# msr502.net
KiCad netlist of a schematic drawn in Altium Designer
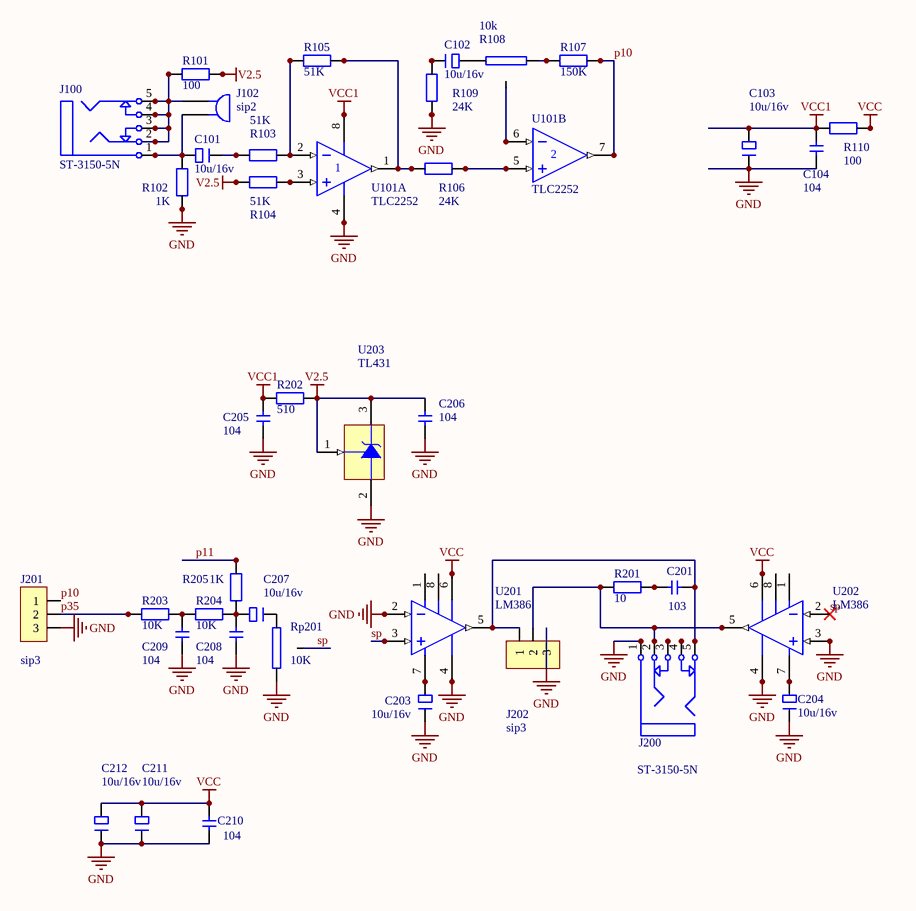
[diagram p0: msr502.SchDoc]

(export (version "E")
  (design (tool "Eeschema 10.0.6"))
  (components
    (comp (ref "C101")
      (value "10u/16v")
      (footprint "rb.1/.2")
      (description "Electrolytic Capacitor")
      (libsource (lib "msr3") (part "ELECTRO1"))
    )
    (comp (ref "C102")
      (value "10u/16v")
      (footprint "rb.1/.2")
      (description "Electrolytic Capacitor")
      (libsource (lib "msr3") (part "ELECTRO1"))
    )
    (comp (ref "C103")
      (value "10u/16v")
      (footprint "rb.1/.2")
      (description "Electrolytic Capacitor")
      (libsource (lib "msr3") (part "ELECTRO1"))
    )
    (comp (ref "C104")
      (value "104")
      (footprint "CAP010805")
      (description "Capacitor")
      (libsource (lib "*") (part "CAP"))
    )
    (comp (ref "C201")
      (value "103")
      (footprint "cap0.1")
      (description "Capacitor")
      (libsource (lib "m2t1") (part "CAP"))
    )
    (comp (ref "C203")
      (value "10u/16v")
      (footprint "rb.1/.2")
      (description "Electrolytic Capacitor")
      (libsource (lib "msr3") (part "ELECTRO1"))
    )
    (comp (ref "C204")
      (value "10u/16v")
      (footprint "rb.1/.2")
      (description "Electrolytic Capacitor")
      (libsource (lib "msr3") (part "ELECTRO1"))
    )
    (comp (ref "C205")
      (value "104")
      (footprint "CAP010805")
      (description "Capacitor")
      (libsource (lib "m2t1") (part "CAP"))
    )
    (comp (ref "C206")
      (value "104")
      (footprint "CAP010805")
      (description "Capacitor")
      (libsource (lib "m2t1") (part "CAP"))
    )
    (comp (ref "C207")
      (value "10u/16v")
      (footprint "rb.1/.2")
      (description "Electrolytic Capacitor")
      (libsource (lib "msr3") (part "ELECTRO1"))
    )
    (comp (ref "C208")
      (value "104")
      (footprint "CAP010805")
      (description "Capacitor")
      (libsource (lib "m2t1") (part "CAP"))
    )
    (comp (ref "C209")
      (value "104")
      (footprint "CAP010805")
      (description "Capacitor")
      (libsource (lib "m2t1") (part "CAP"))
    )
    (comp (ref "C210")
      (value "104")
      (footprint "CAP010805")
      (description "Capacitor")
      (libsource (lib "*") (part "CAP"))
    )
    (comp (ref "C211")
      (value "10u/16v")
      (footprint "rb.1/.2")
      (description "Electrolytic Capacitor")
      (libsource (lib "msr3") (part "ELECTRO1"))
    )
    (comp (ref "C212")
      (value "10u/16v")
      (footprint "rb.1/.2")
      (description "Electrolytic Capacitor")
      (libsource (lib "msr3") (part "ELECTRO1"))
    )
    (comp (ref "J100")
      (value "ST-3150-5N")
      (footprint "ST-3150-5N")
      (description "3-Conductor Jack with 2 break contacts (normals) and 2 auxiliary make contacts")
      (fields (field (name "Comment") "Phonejack Stereo SW") (field (name "PUBLISHER") "Altium Limited"))
      (libsource (lib "mtr1_4") (part "Phonejack Stereo SW"))
    )
    (comp (ref "J102")
      (value "sip2")
      (footprint "PIN2")
      (description "Microphone")
      (fields (field (name "Comment") "pow") (field (name "PUBLISHER") "Altium Limited"))
      (libsource (lib "Miscellaneous Devices") (part "Mic1"))
    )
    (comp (ref "J200")
      (value "ST-3150-5N")
      (footprint "ST-3150-5N")
      (description "3-Conductor Jack with 2 break contacts (normals) and 2 auxiliary make contacts")
      (fields (field (name "Comment") "Phonejack Stereo SW") (field (name "PUBLISHER") "Altium Limited"))
      (libsource (lib "mtr1_4") (part "Phonejack Stereo SW"))
    )
    (comp (ref "J201")
      (value "sip3")
      (footprint "SIP3")
      (description "Connector")
      (fields (field (name "Comment") "CON3"))
      (libsource (lib "m2t1") (part "CON3"))
    )
    (comp (ref "J202")
      (value "sip3")
      (footprint "SIP3")
      (description "Connector")
      (fields (field (name "Comment") "CON3"))
      (libsource (lib "mtr1_1") (part "CON3"))
    )
    (comp (ref "R101")
      (value "100")
      (footprint "a038050")
      (description "Resistor")
      (fields (field (name "Comment") "Res2") (field (name "PUBLISHER") "Altium Limited"))
      (libsource (lib "") (part "Res22_1"))
    )
    (comp (ref "R102")
      (value "1K")
      (footprint "a038050")
      (description "Resistor")
      (fields (field (name "Comment") "Res2") (field (name "PUBLISHER") "Altium Limited"))
      (libsource (lib "") (part "Res22_3"))
    )
    (comp (ref "R103")
      (value "51K")
      (footprint "a038050")
      (description "Resistor")
      (fields (field (name "Comment") "Res2") (field (name "PUBLISHER") "Altium Limited"))
      (libsource (lib "msr4") (part "Res22"))
    )
    (comp (ref "R104")
      (value "51K")
      (footprint "a038050")
      (description "Resistor")
      (fields (field (name "Comment") "Res2") (field (name "PUBLISHER") "Altium Limited"))
      (libsource (lib "msr4") (part "Res22"))
    )
    (comp (ref "R105")
      (value "51K")
      (footprint "a038050")
      (description "Resistor")
      (fields (field (name "Comment") "Res2") (field (name "PUBLISHER") "Altium Limited"))
      (libsource (lib "") (part "Res22_1"))
    )
    (comp (ref "R106")
      (value "24K")
      (footprint "a038050")
      (description "Resistor")
      (fields (field (name "Comment") "Res2") (field (name "PUBLISHER") "Altium Limited"))
      (libsource (lib "") (part "Res22_1"))
    )
    (comp (ref "R107")
      (value "150K")
      (footprint "a038050")
      (description "Resistor")
      (fields (field (name "Comment") "Res2") (field (name "PUBLISHER") "Altium Limited"))
      (libsource (lib "") (part "Res22_1"))
    )
    (comp (ref "R108")
      (value "10k")
      (footprint "VR3296-1")
      (description "3296")
      (libsource (lib "MyLib") (part "RES3"))
    )
    (comp (ref "R109")
      (value "24K")
      (footprint "a038050")
      (description "Resistor")
      (fields (field (name "Comment") "Res2") (field (name "PUBLISHER") "Altium Limited"))
      (libsource (lib "") (part "Res22_2"))
    )
    (comp (ref "R110")
      (value "100")
      (footprint "a038050")
      (description "Resistor")
      (fields (field (name "Comment") "Res2") (field (name "PUBLISHER") "Altium Limited"))
      (libsource (lib "") (part "Res22_1"))
    )
    (comp (ref "R201")
      (value "10")
      (footprint "a038050")
      (description "Resistor")
      (fields (field (name "Comment") "Res2") (field (name "PUBLISHER") "Altium Limited"))
      (libsource (lib "") (part "Res22_1"))
    )
    (comp (ref "R202")
      (value "510")
      (footprint "a038050")
      (description "Resistor")
      (fields (field (name "Comment") "Res2") (field (name "PUBLISHER") "Altium Limited"))
      (libsource (lib "") (part "Res22_1"))
    )
    (comp (ref "R203")
      (value "10K")
      (footprint "a038050")
      (description "Resistor")
      (fields (field (name "Comment") "Res2") (field (name "PUBLISHER") "Altium Limited"))
      (libsource (lib "") (part "Res22_1"))
    )
    (comp (ref "R204")
      (value "10K")
      (footprint "a038050")
      (description "Resistor")
      (fields (field (name "Comment") "Res2") (field (name "PUBLISHER") "Altium Limited"))
      (libsource (lib "") (part "Res22_1"))
    )
    (comp (ref "R205")
      (value "1K")
      (footprint "a038050")
      (description "Resistor")
      (fields (field (name "Comment") "Res2") (field (name "PUBLISHER") "Altium Limited"))
      (libsource (lib "") (part "Res22_2"))
    )
    (comp (ref "Rp201")
      (value "10K")
      (footprint "VR3296-1")
      (description "3296")
      (fields (field (name "Comment") "10k"))
      (libsource (lib "MyLib") (part "RES3"))
    )
    (comp (ref "U101")
      (value "TLC2252")
      (footprint "DS-8")
      (description "Dual Low-Power Operational Amplifier")
      (fields (field (name "PUBLISHER") "Altium Limited"))
      (libsource (lib "msr4") (part "LM358ds"))
    )
    (comp (ref "U201")
      (value "LM386")
      (footprint "DS-8")
      (description "Low Voltage Audio Power Amplifier")
      (fields (field (name "PARTNUMBER") "LM386N-1") (field (name "MANUFACTURER") "National Semiconductor"))
      (libsource (lib "msr4") (part "LM386ds"))
    )
    (comp (ref "U202")
      (value "LM386")
      (footprint "DS-8")
      (description "Low Voltage Audio Power Amplifier")
      (fields (field (name "PARTNUMBER") "LM386N-1") (field (name "MANUFACTURER") "National Semiconductor"))
      (libsource (lib "msr4") (part "LM386ds"))
    )
    (comp (ref "U203")
      (value "TL431")
      (footprint "29-04")
      (description "Programmable Precision Reference")
      (fields (field (name "Comment") "TL431AILP") (field (name "PUBLISHER") "Altium Limited"))
      (libsource (lib "ON Semi Power Mgt Voltage Reference") (part "TL431AILP"))
    )
  )
  (nets
    (net (code "1") (name "/p10") (class "Default")
      (node (ref "J201") (pin "1") (pinfunction "1_1") (pintype "passive"))
      (node (ref "R107") (pin "2") (pinfunction "2_2") (pintype "passive"))
      (node (ref "R107") (pin "4") (pinfunction "4_4") (pintype "passive"))
      (node (ref "U101") (pin "17") (pinfunction "17_17") (pintype "passive"))
      (node (ref "U101") (pin "7") (pinfunction "OUT_7") (pintype "output"))
    )
    (net (code "2") (name "/p11") (class "Default")
      (node (ref "R205") (pin "2") (pinfunction "2_2") (pintype "passive"))
      (node (ref "R205") (pin "4") (pinfunction "4_4") (pintype "passive"))
    )
    (net (code "3") (name "/p35") (class "Default")
      (node (ref "J201") (pin "2") (pinfunction "2_2") (pintype "passive"))
      (node (ref "R203") (pin "1") (pinfunction "1_1") (pintype "passive"))
      (node (ref "R203") (pin "3") (pinfunction "3_3") (pintype "passive"))
    )
    (net (code "4") (name "/sp") (class "Default")
      (node (ref "Rp201") (pin "2") (pintype "passive"))
      (node (ref "U201") (pin "13") (pinfunction "13_13") (pintype "passive"))
      (node (ref "U201") (pin "3") (pinfunction "IN+_3") (pintype "input"))
      (node (ref "U202") (pin "12") (pinfunction "12_12") (pintype "passive"))
      (node (ref "U202") (pin "2") (pinfunction "IN-_2") (pintype "input"))
    )
    (net (code "5") (name "GND") (class "Default")
      (node (ref "C103") (pin "1") (pinfunction "1_1") (pintype "passive"))
      (node (ref "C104") (pin "2") (pinfunction "2_2") (pintype "passive"))
      (node (ref "C203") (pin "1") (pinfunction "1_1") (pintype "passive"))
      (node (ref "C204") (pin "1") (pinfunction "1_1") (pintype "passive"))
      (node (ref "C205") (pin "2") (pinfunction "2_2") (pintype "passive"))
      (node (ref "C206") (pin "2") (pinfunction "2_2") (pintype "passive"))
      (node (ref "C208") (pin "2") (pinfunction "2_2") (pintype "passive"))
      (node (ref "C209") (pin "2") (pinfunction "2_2") (pintype "passive"))
      (node (ref "C210") (pin "2") (pinfunction "2_2") (pintype "passive"))
      (node (ref "C211") (pin "1") (pinfunction "1_1") (pintype "passive"))
      (node (ref "C212") (pin "1") (pinfunction "1_1") (pintype "passive"))
      (node (ref "J200") (pin "1") (pinfunction "1_1") (pintype "passive"))
      (node (ref "J200") (pin "1A") (pinfunction "1A_1A") (pintype "passive"))
      (node (ref "J200") (pin "1B") (pinfunction "1B_1B") (pintype "passive"))
      (node (ref "J201") (pin "3") (pinfunction "3_3") (pintype "passive"))
      (node (ref "J202") (pin "3") (pinfunction "3_3") (pintype "passive"))
      (node (ref "R102") (pin "2") (pinfunction "2_2") (pintype "passive"))
      (node (ref "R102") (pin "4") (pinfunction "4_4") (pintype "passive"))
      (node (ref "R109") (pin "1") (pinfunction "1_1") (pintype "passive"))
      (node (ref "R109") (pin "3") (pinfunction "3_3") (pintype "passive"))
      (node (ref "Rp201") (pin "1") (pintype "passive"))
      (node (ref "U101") (pin "14") (pinfunction "14_14") (pintype "passive"))
      (node (ref "U101") (pin "4") (pinfunction "4_4") (pintype "passive"))
      (node (ref "U201") (pin "12") (pinfunction "12_12") (pintype "passive"))
      (node (ref "U201") (pin "14") (pinfunction "14_14") (pintype "passive"))
      (node (ref "U201") (pin "2") (pinfunction "IN-_2") (pintype "input"))
      (node (ref "U201") (pin "4") (pinfunction "GND_4") (pintype "power_in"))
      (node (ref "U202") (pin "13") (pinfunction "13_13") (pintype "passive"))
      (node (ref "U202") (pin "14") (pinfunction "14_14") (pintype "passive"))
      (node (ref "U202") (pin "3") (pinfunction "IN+_3") (pintype "input"))
      (node (ref "U202") (pin "4") (pinfunction "GND_4") (pintype "power_in"))
      (node (ref "U203") (pin "2") (pinfunction "A_2") (pintype "passive"))
    )
    (net (code "6") (name "Net-(C101-Pad1)") (class "Default")
      (node (ref "C101") (pin "1") (pinfunction "1_1") (pintype "passive"))
      (node (ref "R103") (pin "2") (pinfunction "2_2") (pintype "passive"))
      (node (ref "R103") (pin "4") (pinfunction "4_4") (pintype "passive"))
    )
    (net (code "7") (name "Net-(C101-Pad2)") (class "Default")
      (node (ref "C101") (pin "2") (pinfunction "2_2") (pintype "passive"))
      (node (ref "J100") (pin "1") (pinfunction "1_1") (pintype "passive"))
      (node (ref "J100") (pin "1A") (pinfunction "1A_1A") (pintype "passive"))
      (node (ref "J100") (pin "1B") (pinfunction "1B_1B") (pintype "passive"))
      (node (ref "J102") (pin "2") (pinfunction "2_2") (pintype "passive"))
      (node (ref "R102") (pin "1") (pinfunction "1_1") (pintype "passive"))
      (node (ref "R102") (pin "3") (pinfunction "3_3") (pintype "passive"))
    )
    (net (code "8") (name "Net-(C102-Pad1)") (class "Default")
      (node (ref "C102") (pin "1") (pinfunction "1_1") (pintype "passive"))
      (node (ref "R109") (pin "2") (pinfunction "2_2") (pintype "passive"))
      (node (ref "R109") (pin "4") (pinfunction "4_4") (pintype "passive"))
    )
    (net (code "9") (name "Net-(C102-Pad2)") (class "Default")
      (node (ref "C102") (pin "2") (pinfunction "2_2") (pintype "passive"))
      (node (ref "R108") (pin "1") (pintype "passive"))
    )
    (net (code "10") (name "Net-(C201-Pad1)") (class "Default")
      (node (ref "C201") (pin "1") (pinfunction "1_1") (pintype "passive"))
      (node (ref "R201") (pin "2") (pinfunction "2_2") (pintype "passive"))
      (node (ref "R201") (pin "4") (pinfunction "4_4") (pintype "passive"))
    )
    (net (code "11") (name "Net-(C207-Pad1)") (class "Default")
      (node (ref "C207") (pin "1") (pinfunction "1_1") (pintype "passive"))
      (node (ref "Rp201") (pin "3") (pintype "passive"))
    )
    (net (code "12") (name "Net-(C207-Pad2)") (class "Default")
      (node (ref "C207") (pin "2") (pinfunction "2_2") (pintype "passive"))
      (node (ref "C208") (pin "1") (pinfunction "1_1") (pintype "passive"))
      (node (ref "R204") (pin "2") (pinfunction "2_2") (pintype "passive"))
      (node (ref "R204") (pin "4") (pinfunction "4_4") (pintype "passive"))
      (node (ref "R205") (pin "1") (pinfunction "1_1") (pintype "passive"))
      (node (ref "R205") (pin "3") (pinfunction "3_3") (pintype "passive"))
    )
    (net (code "13") (name "Net-(C209-Pad1)") (class "Default")
      (node (ref "C209") (pin "1") (pinfunction "1_1") (pintype "passive"))
      (node (ref "R203") (pin "2") (pinfunction "2_2") (pintype "passive"))
      (node (ref "R203") (pin "4") (pinfunction "4_4") (pintype "passive"))
      (node (ref "R204") (pin "1") (pinfunction "1_1") (pintype "passive"))
      (node (ref "R204") (pin "3") (pinfunction "3_3") (pintype "passive"))
    )
    (net (code "14") (name "Net-(J100-Pad2)") (class "Default")
      (node (ref "J100") (pin "2") (pinfunction "2_2") (pintype "passive"))
      (node (ref "J100") (pin "2A") (pinfunction "2A_2A") (pintype "passive"))
      (node (ref "J100") (pin "2B") (pinfunction "2B_2B") (pintype "passive"))
      (node (ref "J100") (pin "3") (pinfunction "3_3") (pintype "passive"))
      (node (ref "J100") (pin "3A") (pinfunction "3A_3A") (pintype "passive"))
      (node (ref "J100") (pin "3B") (pinfunction "3B_3B") (pintype "passive"))
      (node (ref "J100") (pin "4") (pinfunction "4_4") (pintype "passive"))
      (node (ref "J100") (pin "4A") (pinfunction "4A_4A") (pintype "passive"))
      (node (ref "J100") (pin "4B") (pinfunction "4B_4B") (pintype "passive"))
      (node (ref "J100") (pin "5") (pinfunction "5_5") (pintype "passive"))
      (node (ref "J100") (pin "5A") (pinfunction "5A_5A") (pintype "passive"))
      (node (ref "J100") (pin "5B") (pinfunction "5B_5B") (pintype "passive"))
      (node (ref "J102") (pin "1") (pinfunction "1_1") (pintype "passive"))
      (node (ref "R101") (pin "1") (pinfunction "1_1") (pintype "passive"))
      (node (ref "R101") (pin "3") (pinfunction "3_3") (pintype "passive"))
    )
    (net (code "15") (name "Net-(J200-Pad3)") (class "Default")
      (node (ref "J200") (pin "3") (pinfunction "3_3") (pintype "passive"))
      (node (ref "J200") (pin "3A") (pinfunction "3A_3A") (pintype "passive"))
      (node (ref "J200") (pin "3B") (pinfunction "3B_3B") (pintype "passive"))
    )
    (net (code "16") (name "Net-(J200-Pad4)") (class "Default")
      (node (ref "J200") (pin "4") (pinfunction "4_4") (pintype "passive"))
      (node (ref "J200") (pin "4A") (pinfunction "4A_4A") (pintype "passive"))
      (node (ref "J200") (pin "4B") (pinfunction "4B_4B") (pintype "passive"))
    )
    (net (code "17") (name "Net-(R107-Pad1)") (class "Default")
      (node (ref "R107") (pin "1") (pinfunction "1_1") (pintype "passive"))
      (node (ref "R107") (pin "3") (pinfunction "3_3") (pintype "passive"))
      (node (ref "R108") (pin "3") (pintype "passive"))
    )
    (net (code "18") (name "Net-(U101A-IN+)") (class "Default")
      (node (ref "R104") (pin "1") (pinfunction "1_1") (pintype "passive"))
      (node (ref "R104") (pin "3") (pinfunction "3_3") (pintype "passive"))
      (node (ref "U101") (pin "13") (pinfunction "13_13") (pintype "passive"))
      (node (ref "U101") (pin "3") (pinfunction "IN+_3") (pintype "input"))
    )
    (net (code "19") (name "Net-(U101A-IN-)") (class "Default")
      (node (ref "R103") (pin "1") (pinfunction "1_1") (pintype "passive"))
      (node (ref "R103") (pin "3") (pinfunction "3_3") (pintype "passive"))
      (node (ref "R105") (pin "1") (pinfunction "1_1") (pintype "passive"))
      (node (ref "R105") (pin "3") (pinfunction "3_3") (pintype "passive"))
      (node (ref "U101") (pin "12") (pinfunction "12_12") (pintype "passive"))
      (node (ref "U101") (pin "2") (pinfunction "IN-_2") (pintype "input"))
    )
    (net (code "20") (name "Net-(U101A-OUT)") (class "Default")
      (node (ref "R105") (pin "2") (pinfunction "2_2") (pintype "passive"))
      (node (ref "R105") (pin "4") (pinfunction "4_4") (pintype "passive"))
      (node (ref "R106") (pin "1") (pinfunction "1_1") (pintype "passive"))
      (node (ref "R106") (pin "3") (pinfunction "3_3") (pintype "passive"))
      (node (ref "U101") (pin "1") (pinfunction "OUT_1") (pintype "output"))
      (node (ref "U101") (pin "11") (pinfunction "11_11") (pintype "passive"))
    )
    (net (code "21") (name "Net-(U101B-IN+)") (class "Default")
      (node (ref "R106") (pin "2") (pinfunction "2_2") (pintype "passive"))
      (node (ref "R106") (pin "4") (pinfunction "4_4") (pintype "passive"))
      (node (ref "U101") (pin "15") (pinfunction "15_15") (pintype "passive"))
      (node (ref "U101") (pin "5") (pinfunction "IN+_5") (pintype "input"))
    )
    (net (code "22") (name "Net-(U101B-IN-)") (class "Default")
      (node (ref "R108") (pin "2") (pintype "passive"))
      (node (ref "U101") (pin "16") (pinfunction "16_16") (pintype "passive"))
      (node (ref "U101") (pin "6") (pinfunction "IN-_6") (pintype "input"))
    )
    (net (code "23") (name "Net-(U201-BYPASS)") (class "Default")
      (node (ref "C203") (pin "2") (pinfunction "2_2") (pintype "passive"))
      (node (ref "U201") (pin "17") (pinfunction "17_17") (pintype "passive"))
      (node (ref "U201") (pin "7") (pinfunction "BYPASS_7") (pintype "passive"))
    )
    (net (code "24") (name "Net-(U201-GAIN-Pad1)") (class "Default")
      (node (ref "U201") (pin "1") (pinfunction "GAIN_1") (pintype "passive"))
      (node (ref "U201") (pin "11") (pinfunction "11_11") (pintype "passive"))
    )
    (net (code "25") (name "Net-(U201-GAIN-Pad8)") (class "Default")
      (node (ref "U201") (pin "18") (pinfunction "18_18") (pintype "passive"))
      (node (ref "U201") (pin "8") (pinfunction "GAIN_8") (pintype "passive"))
    )
    (net (code "26") (name "Net-(U201-OUT)") (class "Default")
      (node (ref "C201") (pin "2") (pinfunction "2_2") (pintype "passive"))
      (node (ref "J200") (pin "5") (pinfunction "5_5") (pintype "passive"))
      (node (ref "J200") (pin "5A") (pinfunction "5A_5A") (pintype "passive"))
      (node (ref "J200") (pin "5B") (pinfunction "5B_5B") (pintype "passive"))
      (node (ref "J202") (pin "1") (pinfunction "1_1") (pintype "passive"))
      (node (ref "U201") (pin "15") (pinfunction "15_15") (pintype "passive"))
      (node (ref "U201") (pin "5") (pinfunction "OUT_5") (pintype "output"))
    )
    (net (code "27") (name "Net-(U202-BYPASS)") (class "Default")
      (node (ref "C204") (pin "2") (pinfunction "2_2") (pintype "passive"))
      (node (ref "U202") (pin "17") (pinfunction "17_17") (pintype "passive"))
      (node (ref "U202") (pin "7") (pinfunction "BYPASS_7") (pintype "passive"))
    )
    (net (code "28") (name "Net-(U202-GAIN-Pad1)") (class "Default")
      (node (ref "U202") (pin "1") (pinfunction "GAIN_1") (pintype "passive"))
      (node (ref "U202") (pin "11") (pinfunction "11_11") (pintype "passive"))
    )
    (net (code "29") (name "Net-(U202-GAIN-Pad8)") (class "Default")
      (node (ref "U202") (pin "18") (pinfunction "18_18") (pintype "passive"))
      (node (ref "U202") (pin "8") (pinfunction "GAIN_8") (pintype "passive"))
    )
    (net (code "30") (name "Net-(U202-OUT)") (class "Default")
      (node (ref "J200") (pin "2") (pinfunction "2_2") (pintype "passive"))
      (node (ref "J200") (pin "2A") (pinfunction "2A_2A") (pintype "passive"))
      (node (ref "J200") (pin "2B") (pinfunction "2B_2B") (pintype "passive"))
      (node (ref "J202") (pin "2") (pinfunction "2_2") (pintype "passive"))
      (node (ref "R201") (pin "1") (pinfunction "1_1") (pintype "passive"))
      (node (ref "R201") (pin "3") (pinfunction "3_3") (pintype "passive"))
      (node (ref "U202") (pin "15") (pinfunction "15_15") (pintype "passive"))
      (node (ref "U202") (pin "5") (pinfunction "OUT_5") (pintype "output"))
    )
    (net (code "31") (name "V2.5") (class "Default")
      (node (ref "C206") (pin "1") (pinfunction "1_1") (pintype "passive"))
      (node (ref "R101") (pin "2") (pinfunction "2_2") (pintype "passive"))
      (node (ref "R101") (pin "4") (pinfunction "4_4") (pintype "passive"))
      (node (ref "R104") (pin "2") (pinfunction "2_2") (pintype "passive"))
      (node (ref "R104") (pin "4") (pinfunction "4_4") (pintype "passive"))
      (node (ref "R202") (pin "2") (pinfunction "2_2") (pintype "passive"))
      (node (ref "R202") (pin "4") (pinfunction "4_4") (pintype "passive"))
      (node (ref "U203") (pin "1") (pinfunction "REF_1") (pintype "input"))
      (node (ref "U203") (pin "3") (pinfunction "K_3") (pintype "passive"))
    )
    (net (code "32") (name "VCC") (class "Default")
      (node (ref "C210") (pin "1") (pinfunction "1_1") (pintype "passive"))
      (node (ref "C211") (pin "2") (pinfunction "2_2") (pintype "passive"))
      (node (ref "C212") (pin "2") (pinfunction "2_2") (pintype "passive"))
      (node (ref "R110") (pin "2") (pinfunction "2_2") (pintype "passive"))
      (node (ref "R110") (pin "4") (pinfunction "4_4") (pintype "passive"))
      (node (ref "U201") (pin "16") (pinfunction "16_16") (pintype "passive"))
      (node (ref "U201") (pin "6") (pinfunction "VS_6") (pintype "power_in"))
      (node (ref "U202") (pin "16") (pinfunction "16_16") (pintype "passive"))
      (node (ref "U202") (pin "6") (pinfunction "VS_6") (pintype "power_in"))
    )
    (net (code "33") (name "VCC1") (class "Default")
      (node (ref "C103") (pin "2") (pinfunction "2_2") (pintype "passive"))
      (node (ref "C104") (pin "1") (pinfunction "1_1") (pintype "passive"))
      (node (ref "C205") (pin "1") (pinfunction "1_1") (pintype "passive"))
      (node (ref "R110") (pin "1") (pinfunction "1_1") (pintype "passive"))
      (node (ref "R110") (pin "3") (pinfunction "3_3") (pintype "passive"))
      (node (ref "R202") (pin "1") (pinfunction "1_1") (pintype "passive"))
      (node (ref "R202") (pin "3") (pinfunction "3_3") (pintype "passive"))
      (node (ref "U101") (pin "18") (pinfunction "18_18") (pintype "passive"))
      (node (ref "U101") (pin "8") (pinfunction "8_8") (pintype "passive"))
    )
  )
)
